# LightWand_USB_power.net
KiCad netlist of a schematic drawn in EAGLE
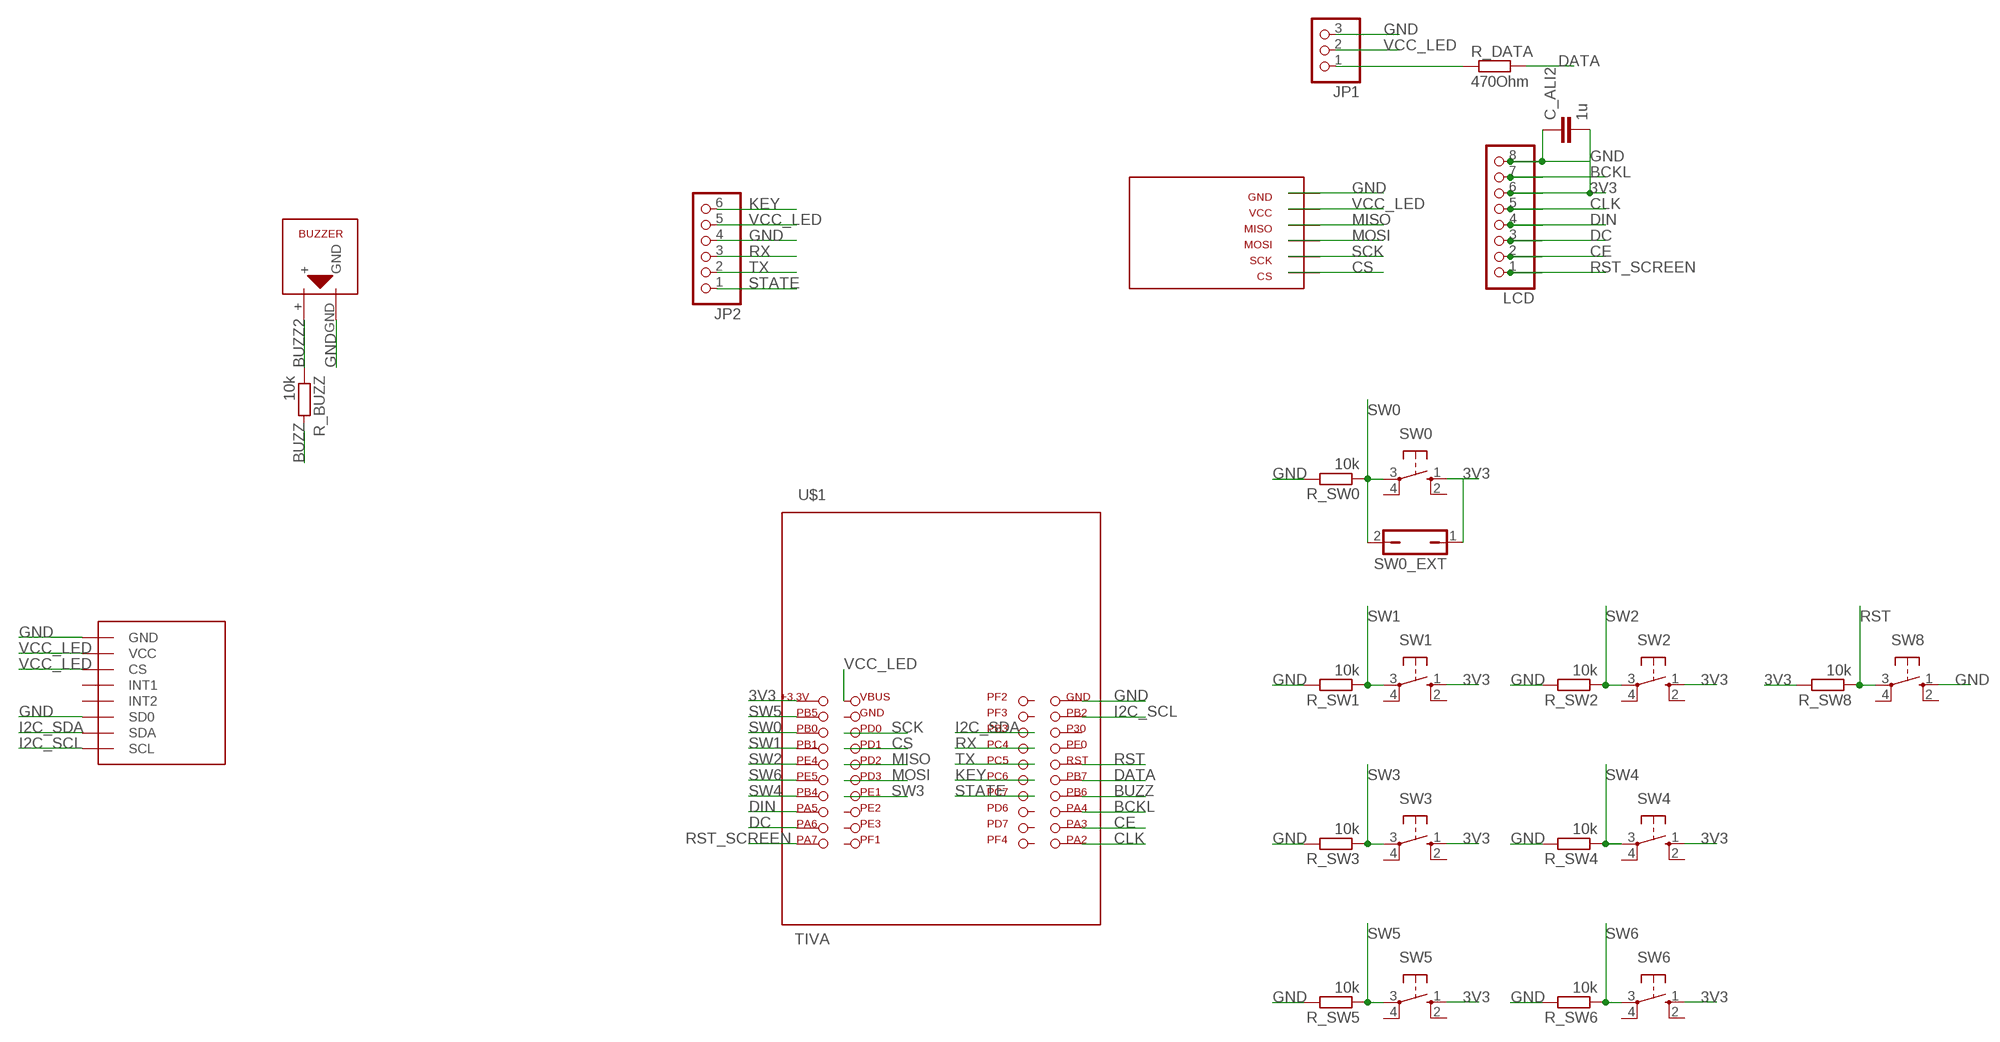
[diagram p0: schematic, sheet 1]

(export (version "E")
  (design (tool "Eeschema 10.0.6"))
  (components
    (comp (ref "C_ALI2")
      (value "1u")
      (footprint "eagle-import:C1206")
      (libsource (lib "eagle-import") (part "C-EUC1206"))
    )
    (comp (ref "JP1")
      (value "PINHD-1X3")
      (footprint "eagle-import:1X03")
      (libsource (lib "eagle-import") (part "PINHD-1X3"))
    )
    (comp (ref "JP2")
      (value "PINHD-1X6")
      (footprint "eagle-import:1X06")
      (libsource (lib "eagle-import") (part "PINHD-1X6"))
    )
    (comp (ref "LCD")
      (value "PINHD-1X8")
      (footprint "eagle-import:1X08")
      (libsource (lib "eagle-import") (part "PINHD-1X8"))
    )
    (comp (ref "R_BUZZ")
      (value "10k")
      (footprint "eagle-import:R1206")
      (libsource (lib "eagle-import") (part "R-EU_R1206"))
    )
    (comp (ref "R_DATA")
      (value "470Ohm")
      (footprint "eagle-import:R1206")
      (libsource (lib "eagle-import") (part "R-EU_R1206"))
    )
    (comp (ref "R_SW0")
      (value "10k")
      (footprint "eagle-import:R1206")
      (libsource (lib "eagle-import") (part "R-EU_R1206"))
    )
    (comp (ref "R_SW1")
      (value "10k")
      (footprint "eagle-import:R1206")
      (libsource (lib "eagle-import") (part "R-EU_R1206"))
    )
    (comp (ref "R_SW2")
      (value "10k")
      (footprint "eagle-import:R1206")
      (libsource (lib "eagle-import") (part "R-EU_R1206"))
    )
    (comp (ref "R_SW3")
      (value "10k")
      (footprint "eagle-import:R1206")
      (libsource (lib "eagle-import") (part "R-EU_R1206"))
    )
    (comp (ref "R_SW4")
      (value "10k")
      (footprint "eagle-import:R1206")
      (libsource (lib "eagle-import") (part "R-EU_R1206"))
    )
    (comp (ref "R_SW5")
      (value "10k")
      (footprint "eagle-import:R1206")
      (libsource (lib "eagle-import") (part "R-EU_R1206"))
    )
    (comp (ref "R_SW6")
      (value "10k")
      (footprint "eagle-import:R1206")
      (libsource (lib "eagle-import") (part "R-EU_R1206"))
    )
    (comp (ref "R_SW8")
      (value "10k")
      (footprint "eagle-import:R1206")
      (libsource (lib "eagle-import") (part "R-EU_R1206"))
    )
    (comp (ref "SW0")
      (value "10-XX")
      (footprint "eagle-import:B3F-10XX")
      (fields (field (name "MPN") "B3F-1000"))
      (libsource (lib "eagle-import") (part "10-XX"))
    )
    (comp (ref "SW0_EXT")
      (value "JP1Q")
      (footprint "eagle-import:JP1")
      (libsource (lib "eagle-import") (part "JP1Q"))
    )
    (comp (ref "SW1")
      (value "10-XX")
      (footprint "eagle-import:B3F-10XX")
      (fields (field (name "MPN") "B3F-1000"))
      (libsource (lib "eagle-import") (part "10-XX"))
    )
    (comp (ref "SW2")
      (value "10-XX")
      (footprint "eagle-import:B3F-10XX")
      (fields (field (name "MPN") "B3F-1000"))
      (libsource (lib "eagle-import") (part "10-XX"))
    )
    (comp (ref "SW3")
      (value "10-XX")
      (footprint "eagle-import:B3F-10XX")
      (fields (field (name "MPN") "B3F-1000"))
      (libsource (lib "eagle-import") (part "10-XX"))
    )
    (comp (ref "SW4")
      (value "10-XX")
      (footprint "eagle-import:B3F-10XX")
      (fields (field (name "MPN") "B3F-1000"))
      (libsource (lib "eagle-import") (part "10-XX"))
    )
    (comp (ref "SW5")
      (value "10-XX")
      (footprint "eagle-import:B3F-10XX")
      (fields (field (name "MPN") "B3F-1000"))
      (libsource (lib "eagle-import") (part "10-XX"))
    )
    (comp (ref "SW6")
      (value "10-XX")
      (footprint "eagle-import:B3F-10XX")
      (fields (field (name "MPN") "B3F-1000"))
      (libsource (lib "eagle-import") (part "10-XX"))
    )
    (comp (ref "SW8")
      (value "10-XX")
      (footprint "eagle-import:B3F-10XX")
      (fields (field (name "MPN") "B3F-1000"))
      (libsource (lib "eagle-import") (part "10-XX"))
    )
    (comp (ref "U$1")
      (value "TIVA")
      (footprint "eagle-import:TIVACSERIES")
      (libsource (lib "eagle-import") (part "TIVA"))
    )
    (comp (ref "U$2")
      (value "ADXL345")
      (footprint "eagle-import:ADXL345")
      (libsource (lib "eagle-import") (part "ADXL345"))
    )
    (comp (ref "U$3")
      (value "MURATA_BUZZER")
      (footprint "eagle-import:MURATA_BUZZER")
      (libsource (lib "eagle-import") (part "MURATA_BUZZER"))
    )
    (comp (ref "U$4")
      (value "SD_READER_CATALEX")
      (footprint "eagle-import:SD_READER_CATALEX")
      (libsource (lib "eagle-import") (part "SD_READER_CATALEX"))
    )
  )
  (nets
    (net (code "1") (name "/3V3") (class "Default")
      (node (ref "C_ALI2") (pin "2") (pinfunction "2_2") (pintype "passive"))
      (node (ref "LCD") (pin "6") (pinfunction "6_6") (pintype "passive"))
      (node (ref "R_SW8") (pin "2") (pinfunction "2_2") (pintype "passive"))
      (node (ref "SW0") (pin "1") (pinfunction "S_1") (pintype "passive"))
      (node (ref "SW0_EXT") (pin "1") (pinfunction "1_1") (pintype "passive"))
      (node (ref "SW1") (pin "1") (pinfunction "S_1") (pintype "passive"))
      (node (ref "SW2") (pin "1") (pinfunction "S_1") (pintype "passive"))
      (node (ref "SW3") (pin "1") (pinfunction "S_1") (pintype "passive"))
      (node (ref "SW4") (pin "1") (pinfunction "S_1") (pintype "passive"))
      (node (ref "SW5") (pin "1") (pinfunction "S_1") (pintype "passive"))
      (node (ref "SW6") (pin "1") (pinfunction "S_1") (pintype "passive"))
      (node (ref "U$1") (pin "+3.3V") (pinfunction "3.3V_+3.3V") (pintype "bidirectional"))
    )
    (net (code "2") (name "/BCKL") (class "Default")
      (node (ref "LCD") (pin "7") (pinfunction "7_7") (pintype "passive"))
      (node (ref "U$1") (pin "PA4") (pinfunction "PA4_PA4") (pintype "bidirectional"))
    )
    (net (code "3") (name "/BUZZ") (class "Default")
      (node (ref "R_BUZZ") (pin "2") (pinfunction "2_2") (pintype "passive"))
      (node (ref "U$1") (pin "PB6") (pinfunction "PB6_PB6") (pintype "bidirectional"))
    )
    (net (code "4") (name "/BUZZ2") (class "Default")
      (node (ref "R_BUZZ") (pin "1") (pinfunction "1_1") (pintype "passive"))
      (node (ref "U$3") (pin "+") (pinfunction "+_+") (pintype "bidirectional"))
    )
    (net (code "5") (name "/CE") (class "Default")
      (node (ref "LCD") (pin "2") (pinfunction "2_2") (pintype "passive"))
      (node (ref "U$1") (pin "PA3") (pinfunction "PA3_PA3") (pintype "bidirectional"))
    )
    (net (code "6") (name "/CLK") (class "Default")
      (node (ref "LCD") (pin "5") (pinfunction "5_5") (pintype "passive"))
      (node (ref "U$1") (pin "PA2") (pinfunction "PA2_PA2") (pintype "bidirectional"))
    )
    (net (code "7") (name "/CS") (class "Default")
      (node (ref "U$1") (pin "PD1") (pinfunction "PD1_PD1") (pintype "bidirectional"))
      (node (ref "U$4") (pin "CS") (pinfunction "CS_CS") (pintype "bidirectional"))
    )
    (net (code "8") (name "/DATA") (class "Default")
      (node (ref "R_DATA") (pin "2") (pinfunction "2_2") (pintype "passive"))
      (node (ref "U$1") (pin "PB7") (pinfunction "PB7_PB7") (pintype "bidirectional"))
    )
    (net (code "9") (name "/DC") (class "Default")
      (node (ref "LCD") (pin "3") (pinfunction "3_3") (pintype "passive"))
      (node (ref "U$1") (pin "PA6") (pinfunction "PA6_PA6") (pintype "bidirectional"))
    )
    (net (code "10") (name "/DIN") (class "Default")
      (node (ref "LCD") (pin "4") (pinfunction "4_4") (pintype "passive"))
      (node (ref "U$1") (pin "PA5") (pinfunction "PA5_PA5") (pintype "bidirectional"))
    )
    (net (code "11") (name "/GND") (class "Default")
      (node (ref "C_ALI2") (pin "1") (pinfunction "1_1") (pintype "passive"))
      (node (ref "JP1") (pin "3") (pinfunction "3_3") (pintype "passive"))
      (node (ref "JP2") (pin "4") (pinfunction "4_4") (pintype "passive"))
      (node (ref "LCD") (pin "8") (pinfunction "8_8") (pintype "passive"))
      (node (ref "R_SW0") (pin "2") (pinfunction "2_2") (pintype "passive"))
      (node (ref "R_SW1") (pin "2") (pinfunction "2_2") (pintype "passive"))
      (node (ref "R_SW2") (pin "2") (pinfunction "2_2") (pintype "passive"))
      (node (ref "R_SW3") (pin "2") (pinfunction "2_2") (pintype "passive"))
      (node (ref "R_SW4") (pin "2") (pinfunction "2_2") (pintype "passive"))
      (node (ref "R_SW5") (pin "2") (pinfunction "2_2") (pintype "passive"))
      (node (ref "R_SW6") (pin "2") (pinfunction "2_2") (pintype "passive"))
      (node (ref "SW8") (pin "1") (pinfunction "S_1") (pintype "passive"))
      (node (ref "U$1") (pin "GND1") (pinfunction "GND2_GND1") (pintype "bidirectional"))
      (node (ref "U$2") (pin "P$1") (pinfunction "GND_P$1") (pintype "bidirectional"))
      (node (ref "U$2") (pin "P$6") (pinfunction "SD0_P$6") (pintype "bidirectional"))
      (node (ref "U$3") (pin "GND") (pinfunction "GND_GND") (pintype "bidirectional"))
      (node (ref "U$4") (pin "GND") (pinfunction "GND_GND") (pintype "bidirectional"))
    )
    (net (code "12") (name "/I2C_SCL") (class "Default")
      (node (ref "U$1") (pin "PB2") (pinfunction "PB2_PB2") (pintype "bidirectional"))
      (node (ref "U$2") (pin "P$7") (pinfunction "SCL_P$7") (pintype "bidirectional"))
    )
    (net (code "13") (name "/I2C_SDA") (class "Default")
      (node (ref "U$1") (pin "PB3") (pinfunction "PB3_PB3") (pintype "bidirectional"))
      (node (ref "U$2") (pin "P$8") (pinfunction "SDA_P$8") (pintype "bidirectional"))
    )
    (net (code "14") (name "/KEY") (class "Default")
      (node (ref "JP2") (pin "6") (pinfunction "6_6") (pintype "passive"))
      (node (ref "U$1") (pin "PC6") (pinfunction "PC6_PC6") (pintype "bidirectional"))
    )
    (net (code "15") (name "/MISO") (class "Default")
      (node (ref "U$1") (pin "PD2") (pinfunction "PD2_PD2") (pintype "bidirectional"))
      (node (ref "U$4") (pin "MISO") (pinfunction "MISO_MISO") (pintype "bidirectional"))
    )
    (net (code "16") (name "/MOSI") (class "Default")
      (node (ref "U$1") (pin "PD3") (pinfunction "PD3_PD3") (pintype "bidirectional"))
      (node (ref "U$4") (pin "MOSI") (pinfunction "MOSI_MOSI") (pintype "bidirectional"))
    )
    (net (code "17") (name "/RST") (class "Default")
      (node (ref "R_SW8") (pin "1") (pinfunction "1_1") (pintype "passive"))
      (node (ref "SW8") (pin "3") (pinfunction "P_3") (pintype "passive"))
      (node (ref "U$1") (pin "RST") (pinfunction "RST_RST") (pintype "bidirectional"))
    )
    (net (code "18") (name "/RST_SCREEN") (class "Default")
      (node (ref "LCD") (pin "1") (pinfunction "1_1") (pintype "passive"))
      (node (ref "U$1") (pin "PA7") (pinfunction "PA7_PA7") (pintype "bidirectional"))
    )
    (net (code "19") (name "/RX") (class "Default")
      (node (ref "JP2") (pin "3") (pinfunction "3_3") (pintype "passive"))
      (node (ref "U$1") (pin "PC4") (pinfunction "PC4_PC4") (pintype "bidirectional"))
    )
    (net (code "20") (name "/SCK") (class "Default")
      (node (ref "U$1") (pin "PD0") (pinfunction "PD0_PD0") (pintype "bidirectional"))
      (node (ref "U$4") (pin "SCK") (pinfunction "SCK_SCK") (pintype "bidirectional"))
    )
    (net (code "21") (name "/STATE") (class "Default")
      (node (ref "JP2") (pin "1") (pinfunction "1_1") (pintype "passive"))
      (node (ref "U$1") (pin "PC7") (pinfunction "PC7_PC7") (pintype "bidirectional"))
    )
    (net (code "22") (name "/SW0") (class "Default")
      (node (ref "R_SW0") (pin "1") (pinfunction "1_1") (pintype "passive"))
      (node (ref "SW0") (pin "3") (pinfunction "P_3") (pintype "passive"))
      (node (ref "SW0_EXT") (pin "2") (pinfunction "2_2") (pintype "passive"))
      (node (ref "U$1") (pin "PB0") (pinfunction "PB0_PB0") (pintype "bidirectional"))
    )
    (net (code "23") (name "/SW1") (class "Default")
      (node (ref "R_SW1") (pin "1") (pinfunction "1_1") (pintype "passive"))
      (node (ref "SW1") (pin "3") (pinfunction "P_3") (pintype "passive"))
      (node (ref "U$1") (pin "PB1") (pinfunction "PB1_PB1") (pintype "bidirectional"))
    )
    (net (code "24") (name "/SW2") (class "Default")
      (node (ref "R_SW2") (pin "1") (pinfunction "1_1") (pintype "passive"))
      (node (ref "SW2") (pin "3") (pinfunction "P_3") (pintype "passive"))
      (node (ref "U$1") (pin "PE4") (pinfunction "PE4_PE4") (pintype "bidirectional"))
    )
    (net (code "25") (name "/SW3") (class "Default")
      (node (ref "R_SW3") (pin "1") (pinfunction "1_1") (pintype "passive"))
      (node (ref "SW3") (pin "3") (pinfunction "P_3") (pintype "passive"))
      (node (ref "U$1") (pin "PE1") (pinfunction "PE1_PE1") (pintype "bidirectional"))
    )
    (net (code "26") (name "/SW4") (class "Default")
      (node (ref "R_SW4") (pin "1") (pinfunction "1_1") (pintype "passive"))
      (node (ref "SW4") (pin "3") (pinfunction "P_3") (pintype "passive"))
      (node (ref "U$1") (pin "PB4") (pinfunction "PB4_PB4") (pintype "bidirectional"))
    )
    (net (code "27") (name "/SW5") (class "Default")
      (node (ref "R_SW5") (pin "1") (pinfunction "1_1") (pintype "passive"))
      (node (ref "SW5") (pin "3") (pinfunction "P_3") (pintype "passive"))
      (node (ref "U$1") (pin "PB5") (pinfunction "PB5_PB5") (pintype "bidirectional"))
    )
    (net (code "28") (name "/SW6") (class "Default")
      (node (ref "R_SW6") (pin "1") (pinfunction "1_1") (pintype "passive"))
      (node (ref "SW6") (pin "3") (pinfunction "P_3") (pintype "passive"))
      (node (ref "U$1") (pin "PE5") (pinfunction "PE5_PE5") (pintype "bidirectional"))
    )
    (net (code "29") (name "/TX") (class "Default")
      (node (ref "JP2") (pin "2") (pinfunction "2_2") (pintype "passive"))
      (node (ref "U$1") (pin "PC5") (pinfunction "PC5_PC5") (pintype "bidirectional"))
    )
    (net (code "30") (name "/VCC_LED") (class "Default")
      (node (ref "JP1") (pin "2") (pinfunction "2_2") (pintype "passive"))
      (node (ref "JP2") (pin "5") (pinfunction "5_5") (pintype "passive"))
      (node (ref "U$1") (pin "VBUS") (pinfunction "VBUS_VBUS") (pintype "passive"))
      (node (ref "U$2") (pin "P$2") (pinfunction "VCC_P$2") (pintype "bidirectional"))
      (node (ref "U$2") (pin "P$3") (pinfunction "CS_P$3") (pintype "bidirectional"))
      (node (ref "U$4") (pin "VCC") (pinfunction "VCC_VCC") (pintype "bidirectional"))
    )
    (net (code "31") (name "Net-(JP1-Pad1)") (class "Default")
      (node (ref "JP1") (pin "1") (pinfunction "1_1") (pintype "passive"))
      (node (ref "R_DATA") (pin "1") (pinfunction "1_1") (pintype "passive"))
    )
    (net (code "32") (name "unconnected-(SW0-P1-Pad4)") (class "Default")
      (node (ref "SW0") (pin "4") (pinfunction "P1_4") (pintype "passive"))
    )
    (net (code "33") (name "unconnected-(SW0-S1-Pad2)") (class "Default")
      (node (ref "SW0") (pin "2") (pinfunction "S1_2") (pintype "passive"))
    )
    (net (code "34") (name "unconnected-(SW1-P1-Pad4)") (class "Default")
      (node (ref "SW1") (pin "4") (pinfunction "P1_4") (pintype "passive"))
    )
    (net (code "35") (name "unconnected-(SW1-S1-Pad2)") (class "Default")
      (node (ref "SW1") (pin "2") (pinfunction "S1_2") (pintype "passive"))
    )
    (net (code "36") (name "unconnected-(SW2-P1-Pad4)") (class "Default")
      (node (ref "SW2") (pin "4") (pinfunction "P1_4") (pintype "passive"))
    )
    (net (code "37") (name "unconnected-(SW2-S1-Pad2)") (class "Default")
      (node (ref "SW2") (pin "2") (pinfunction "S1_2") (pintype "passive"))
    )
    (net (code "38") (name "unconnected-(SW3-P1-Pad4)") (class "Default")
      (node (ref "SW3") (pin "4") (pinfunction "P1_4") (pintype "passive"))
    )
    (net (code "39") (name "unconnected-(SW3-S1-Pad2)") (class "Default")
      (node (ref "SW3") (pin "2") (pinfunction "S1_2") (pintype "passive"))
    )
    (net (code "40") (name "unconnected-(SW4-P1-Pad4)") (class "Default")
      (node (ref "SW4") (pin "4") (pinfunction "P1_4") (pintype "passive"))
    )
    (net (code "41") (name "unconnected-(SW4-S1-Pad2)") (class "Default")
      (node (ref "SW4") (pin "2") (pinfunction "S1_2") (pintype "passive"))
    )
    (net (code "42") (name "unconnected-(SW5-P1-Pad4)") (class "Default")
      (node (ref "SW5") (pin "4") (pinfunction "P1_4") (pintype "passive"))
    )
    (net (code "43") (name "unconnected-(SW5-S1-Pad2)") (class "Default")
      (node (ref "SW5") (pin "2") (pinfunction "S1_2") (pintype "passive"))
    )
    (net (code "44") (name "unconnected-(SW6-P1-Pad4)") (class "Default")
      (node (ref "SW6") (pin "4") (pinfunction "P1_4") (pintype "passive"))
    )
    (net (code "45") (name "unconnected-(SW6-S1-Pad2)") (class "Default")
      (node (ref "SW6") (pin "2") (pinfunction "S1_2") (pintype "passive"))
    )
    (net (code "46") (name "unconnected-(SW8-P1-Pad4)") (class "Default")
      (node (ref "SW8") (pin "4") (pinfunction "P1_4") (pintype "passive"))
    )
    (net (code "47") (name "unconnected-(SW8-S1-Pad2)") (class "Default")
      (node (ref "SW8") (pin "2") (pinfunction "S1_2") (pintype "passive"))
    )
    (net (code "48") (name "unconnected-(U$1-PadGND)") (class "Default")
      (node (ref "U$1") (pin "GND") (pinfunction "GND_GND") (pintype "bidirectional"))
    )
    (net (code "49") (name "unconnected-(U$1-PadP30)") (class "Default")
      (node (ref "U$1") (pin "P30") (pinfunction "P30_P30") (pintype "bidirectional"))
    )
    (net (code "50") (name "unconnected-(U$1-PadPD6)") (class "Default")
      (node (ref "U$1") (pin "PD6") (pinfunction "PD6_PD6") (pintype "bidirectional"))
    )
    (net (code "51") (name "unconnected-(U$1-PadPD7)") (class "Default")
      (node (ref "U$1") (pin "PD7") (pinfunction "PD7_PD7") (pintype "bidirectional"))
    )
    (net (code "52") (name "unconnected-(U$1-PadPE2)") (class "Default")
      (node (ref "U$1") (pin "PE2") (pinfunction "PE2_PE2") (pintype "bidirectional"))
    )
    (net (code "53") (name "unconnected-(U$1-PadPE3)") (class "Default")
      (node (ref "U$1") (pin "PE3") (pinfunction "PE3_PE3") (pintype "bidirectional"))
    )
    (net (code "54") (name "unconnected-(U$1-PadPF0)") (class "Default")
      (node (ref "U$1") (pin "PF0") (pinfunction "PF0_PF0") (pintype "bidirectional"))
    )
    (net (code "55") (name "unconnected-(U$1-PadPF1)") (class "Default")
      (node (ref "U$1") (pin "PF1") (pinfunction "PF1_PF1") (pintype "bidirectional"))
    )
    (net (code "56") (name "unconnected-(U$1-PadPF2)") (class "Default")
      (node (ref "U$1") (pin "PF2") (pinfunction "PF2_PF2") (pintype "bidirectional"))
    )
    (net (code "57") (name "unconnected-(U$1-PadPF3)") (class "Default")
      (node (ref "U$1") (pin "PF3") (pinfunction "PF3_PF3") (pintype "bidirectional"))
    )
    (net (code "58") (name "unconnected-(U$1-PadPF4)") (class "Default")
      (node (ref "U$1") (pin "PF4") (pinfunction "PF4_PF4") (pintype "bidirectional"))
    )
    (net (code "59") (name "unconnected-(U$2-INT1-PadP$4)") (class "Default")
      (node (ref "U$2") (pin "P$4") (pinfunction "INT1_P$4") (pintype "bidirectional"))
    )
    (net (code "60") (name "unconnected-(U$2-INT2-PadP$5)") (class "Default")
      (node (ref "U$2") (pin "P$5") (pinfunction "INT2_P$5") (pintype "bidirectional"))
    )
  )
)
